# MM7150.net
KiCad netlist of a schematic drawn in EAGLE
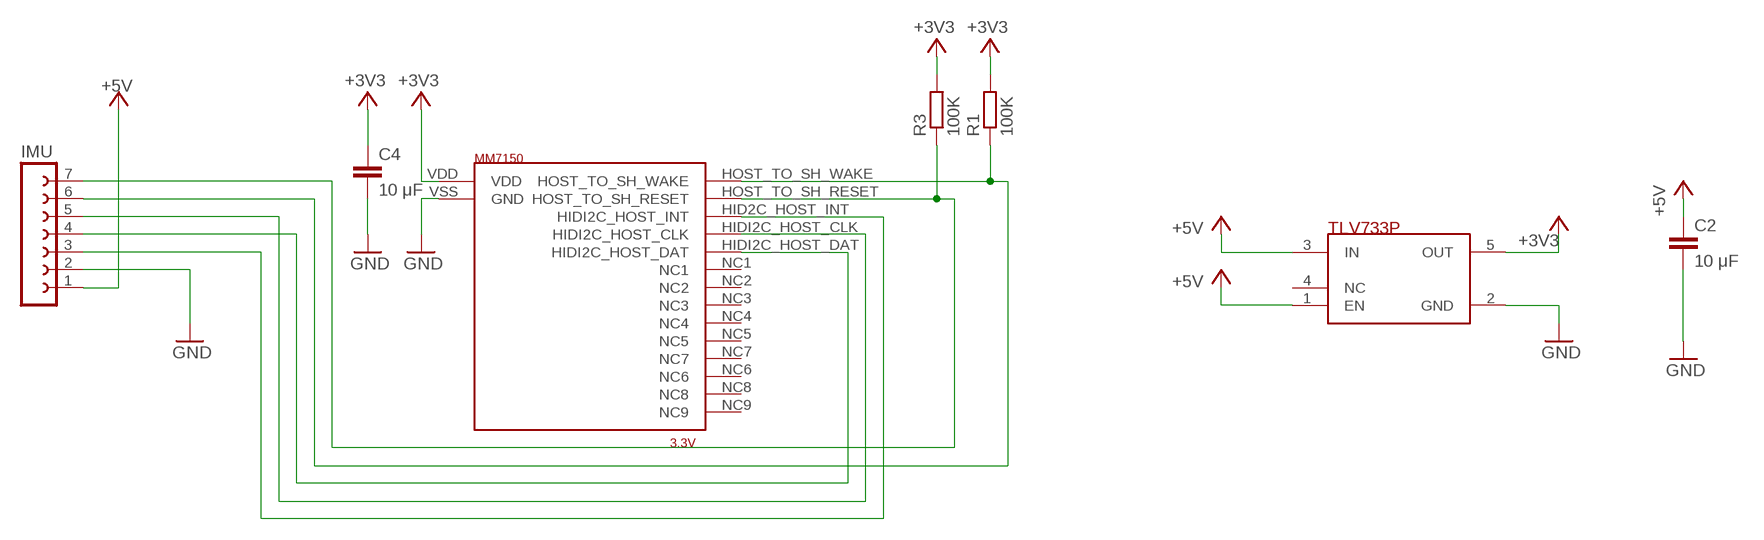
[diagram p0: schematic, sheet 1]

(export (version "E")
  (design (tool "Eeschema 10.0.6"))
  (components
    (comp (ref "C2")
      (value "10 μF")
      (footprint "eagle-import:C0805")
      (libsource (lib "eagle-import") (part "C-EUC0805"))
    )
    (comp (ref "C4")
      (value "10 μF")
      (footprint "eagle-import:C0805")
      (libsource (lib "eagle-import") (part "C-EUC0805"))
    )
    (comp (ref "IMU")
      (value "FE07-1")
      (footprint "eagle-import:FE07")
      (libsource (lib "eagle-import") (part "FE07-1"))
    )
    (comp (ref "R1")
      (value "100K")
      (footprint "eagle-import:R2012")
      (libsource (lib "eagle-import") (part "R-EU_R2012"))
    )
    (comp (ref "R3")
      (value "100K")
      (footprint "eagle-import:R2012")
      (libsource (lib "eagle-import") (part "R-EU_R2012"))
    )
    (comp (ref "U$1")
      (value "MM7150")
      (footprint "eagle-import:MM7150")
      (libsource (lib "eagle-import") (part "MM7150"))
    )
    (comp (ref "U$2")
      (value "TLV733P")
      (footprint "eagle-import:SOT23-5")
      (libsource (lib "eagle-import") (part "TLV733P"))
    )
  )
  (nets
    (net (code "1") (name "+3V3") (class "Default")
      (node (ref "C4") (pin "1") (pinfunction "1_1") (pintype "passive"))
      (node (ref "R1") (pin "2") (pinfunction "2_2") (pintype "passive"))
      (node (ref "R3") (pin "2") (pinfunction "2_2") (pintype "passive"))
      (node (ref "U$1") (pin "VDD") (pinfunction "VDD_VDD") (pintype "bidirectional"))
      (node (ref "U$2") (pin "5") (pinfunction "OUT_5") (pintype "bidirectional"))
    )
    (net (code "2") (name "+5V") (class "Default")
      (node (ref "C2") (pin "1") (pinfunction "1_1") (pintype "passive"))
      (node (ref "IMU") (pin "1") (pinfunction "1_1") (pintype "passive"))
      (node (ref "U$2") (pin "1") (pinfunction "EN_1") (pintype "bidirectional"))
      (node (ref "U$2") (pin "3") (pinfunction "IN_3") (pintype "bidirectional"))
    )
    (net (code "3") (name "GND") (class "Default")
      (node (ref "C2") (pin "2") (pinfunction "2_2") (pintype "passive"))
      (node (ref "C4") (pin "2") (pinfunction "2_2") (pintype "passive"))
      (node (ref "IMU") (pin "2") (pinfunction "2_2") (pintype "passive"))
      (node (ref "U$1") (pin "VSS") (pinfunction "GND_VSS") (pintype "bidirectional"))
      (node (ref "U$2") (pin "2") (pinfunction "GND_2") (pintype "bidirectional"))
    )
    (net (code "4") (name "Net-(IMU-Pad4)") (class "Default")
      (node (ref "IMU") (pin "4") (pinfunction "4_4") (pintype "passive"))
      (node (ref "U$1") (pin "HIDI2C_HOST_DAT") (pinfunction "HIDI2C_HOST_DAT_HIDI2C_HOST_DAT") (pintype "bidirectional"))
    )
    (net (code "5") (name "Net-(IMU-Pad5)") (class "Default")
      (node (ref "IMU") (pin "5") (pinfunction "5_5") (pintype "passive"))
      (node (ref "U$1") (pin "HIDI2C_HOST_CLK") (pinfunction "HIDI2C_HOST_CLK_HIDI2C_HOST_CLK") (pintype "bidirectional"))
    )
    (net (code "6") (name "Net-(IMU-Pad6)") (class "Default")
      (node (ref "IMU") (pin "6") (pinfunction "6_6") (pintype "passive"))
      (node (ref "R1") (pin "1") (pinfunction "1_1") (pintype "passive"))
      (node (ref "U$1") (pin "HOST_TO_SH_WAKE") (pinfunction "HOST_TO_SH_WAKE_HOST_TO_SH_WAKE") (pintype "bidirectional"))
    )
    (net (code "7") (name "Net-(IMU-Pad7)") (class "Default")
      (node (ref "IMU") (pin "7") (pinfunction "7_7") (pintype "passive"))
      (node (ref "R3") (pin "1") (pinfunction "1_1") (pintype "passive"))
      (node (ref "U$1") (pin "HOST_TO_SH_RESET") (pinfunction "HOST_TO_SH_RESET_HOST_TO_SH_RESET") (pintype "bidirectional"))
    )
    (net (code "8") (name "Net-(U$1-HIDI2C_HOST_INT)") (class "Default")
      (node (ref "IMU") (pin "3") (pinfunction "3_3") (pintype "passive"))
      (node (ref "U$1") (pin "HID2C_HOST_INT") (pinfunction "HIDI2C_HOST_INT_HID2C_HOST_INT") (pintype "bidirectional"))
    )
    (net (code "9") (name "unconnected-(U$1-PadNC1)") (class "Default")
      (node (ref "U$1") (pin "NC1") (pinfunction "NC1_NC1") (pintype "bidirectional"))
    )
    (net (code "10") (name "unconnected-(U$1-PadNC2)") (class "Default")
      (node (ref "U$1") (pin "NC2") (pinfunction "NC2_NC2") (pintype "bidirectional"))
    )
    (net (code "11") (name "unconnected-(U$1-PadNC3)") (class "Default")
      (node (ref "U$1") (pin "NC3") (pinfunction "NC3_NC3") (pintype "bidirectional"))
    )
    (net (code "12") (name "unconnected-(U$1-PadNC4)") (class "Default")
      (node (ref "U$1") (pin "NC4") (pinfunction "NC4_NC4") (pintype "bidirectional"))
    )
    (net (code "13") (name "unconnected-(U$1-PadNC5)") (class "Default")
      (node (ref "U$1") (pin "NC5") (pinfunction "NC5_NC5") (pintype "bidirectional"))
    )
    (net (code "14") (name "unconnected-(U$1-PadNC6)") (class "Default")
      (node (ref "U$1") (pin "NC6") (pinfunction "NC6_NC6") (pintype "bidirectional"))
    )
    (net (code "15") (name "unconnected-(U$1-PadNC7)") (class "Default")
      (node (ref "U$1") (pin "NC7") (pinfunction "NC7_NC7") (pintype "bidirectional"))
    )
    (net (code "16") (name "unconnected-(U$1-PadNC8)") (class "Default")
      (node (ref "U$1") (pin "NC8") (pinfunction "NC8_NC8") (pintype "bidirectional"))
    )
    (net (code "17") (name "unconnected-(U$1-PadNC9)") (class "Default")
      (node (ref "U$1") (pin "NC9") (pinfunction "NC9_NC9") (pintype "bidirectional"))
    )
    (net (code "18") (name "unconnected-(U$2-NC-Pad4)") (class "Default")
      (node (ref "U$2") (pin "4") (pinfunction "NC_4") (pintype "bidirectional"))
    )
  )
)
